# Ethernet.net
KiCad netlist of a schematic drawn in Altium Designer
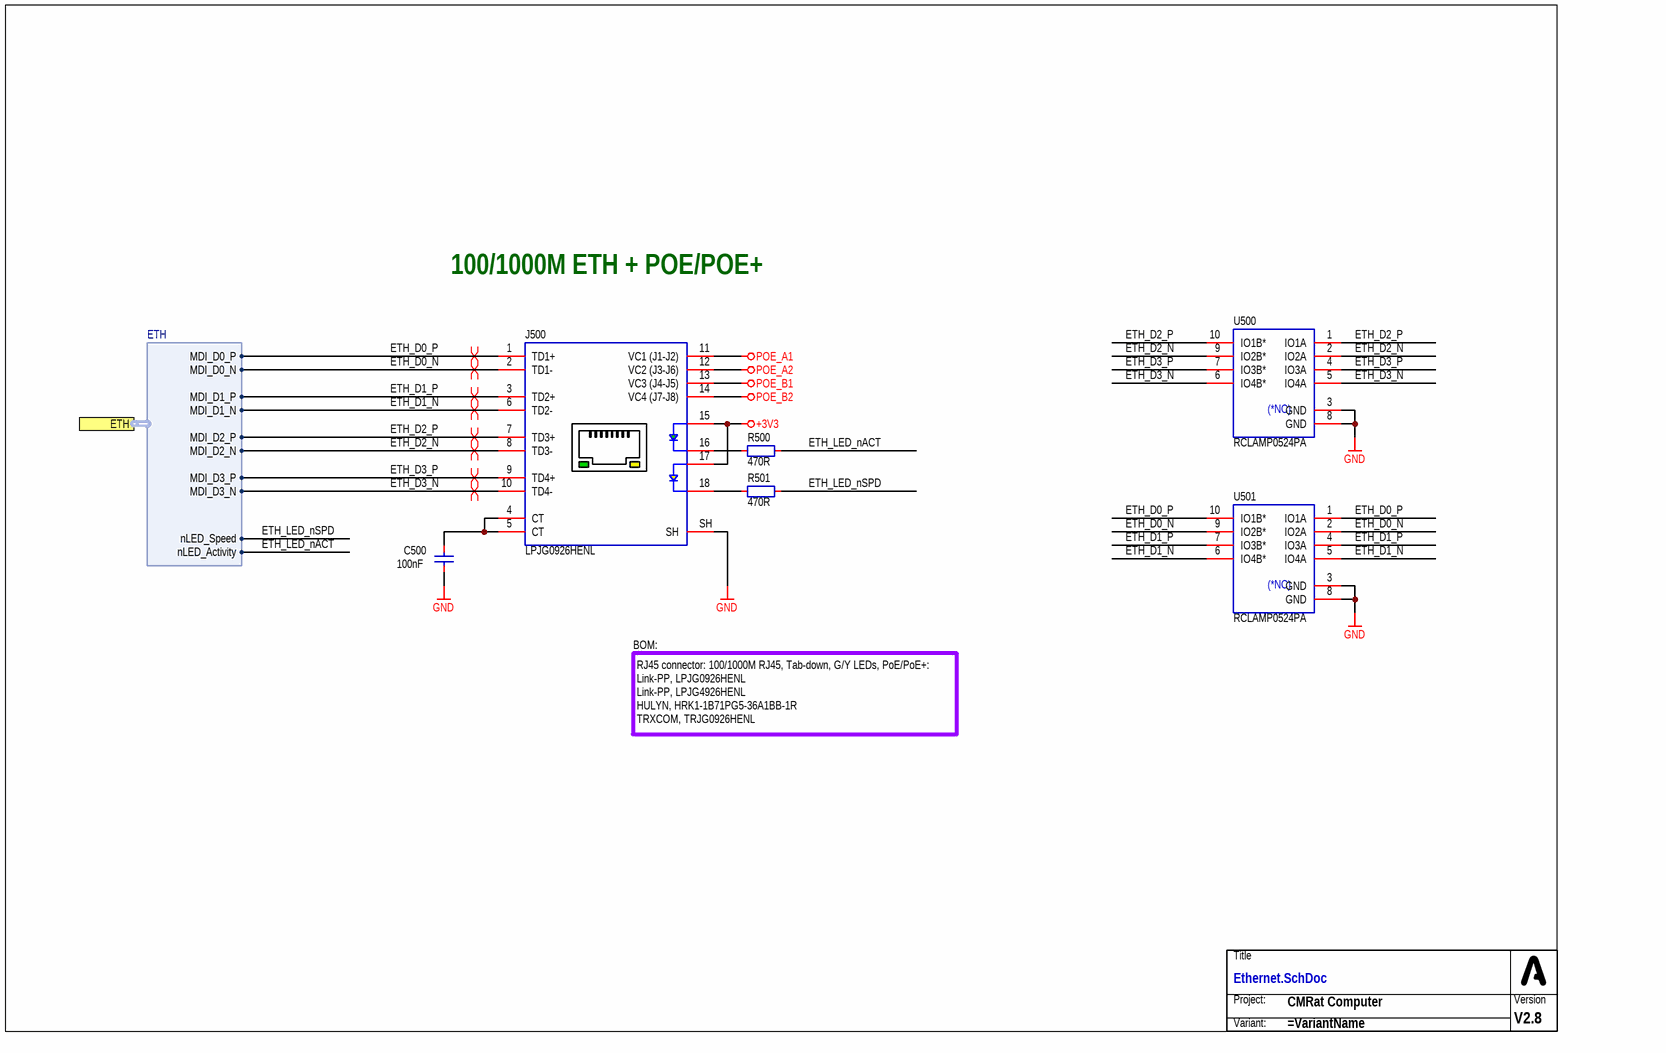
[diagram p0: Ethernet.SchDoc]

(export (version "E")
  (design (tool "Eeschema 10.0.6"))
  (components
    (comp (ref "C500")
      (value "100nF")
      (footprint "CAP_0603_R")
      (description "Capacitor; MLCC; 100nF; 10V X5R")
      (fields (field (name "MANUFACTURER") "YAGEO") (field (name "MPN") "CC0603KRX7R9BB104"))
      (libsource (lib "MirFol_db_local") (part "CAP"))
    )
    (comp (ref "J500")
      (value "LPJG0926HENL")
      (footprint "CON_LPP_LPJG0926HENL")
      (description "Connector; RJ45;")
      (fields (field (name "MANUFACTURER") "Link-PP"))
      (libsource (lib "Pineberry_Lib") (part "CON_LPP_LPJG0926HENL"))
    )
    (comp (ref "R500")
      (value "470R")
      (footprint "RES_0603_R")
      (description "Resistor; Thick Film; 470R; 1%; 100mW; 100PPM; 75V; Standard; SMD; 0603 (1608);")
      (fields (field (name "MANUFACTURER") "UNI-ROYAL(Uniroyal Elec)") (field (name "MPN") "0603WAF4700T5E"))
      (libsource (lib "MirFol_db_local") (part "RES"))
    )
    (comp (ref "R501")
      (value "470R")
      (footprint "RES_0603_R")
      (description "Resistor; Thick Film; 470R; 1%; 100mW; 100PPM; 75V; Standard; SMD; 0603 (1608);")
      (fields (field (name "MANUFACTURER") "UNI-ROYAL(Uniroyal Elec)") (field (name "MPN") "0603WAF4700T5E"))
      (libsource (lib "MirFol_db_local") (part "RES"))
    )
    (comp (ref "TB500") (value "~") (libsource (lib "Symbols_NO_BOM") (part "SCH_TITLE_BLOCK_SIMPLE_NODATE")))
    (comp (ref "U500")
      (value "RCLAMP0524PA")
      (footprint "ICC_SLP2510P8_250X100X60_P50_R")
      (description "IC; TVS Arrays; ESD Protection; 4-Channel; 17kV Air; 12kV Contact; 0.3pF Capitance; TBD; SMD; TBD;")
      (fields (field (name "MANUFACTURER") "Semtech Corporation") (field (name "MPN") "RCLAMP0524PATCT"))
      (libsource (lib "MirFol_db_local") (part "ICC_SMT_RCLAMP0524PA"))
    )
    (comp (ref "U501")
      (value "RCLAMP0524PA")
      (footprint "ICC_SLP2510P8_250X100X60_P50_R")
      (description "IC; TVS Arrays; ESD Protection; 4-Channel; 17kV Air; 12kV Contact; 0.3pF Capitance; TBD; SMD; TBD;")
      (fields (field (name "MANUFACTURER") "Semtech Corporation") (field (name "MPN") "RCLAMP0524PATCT"))
      (libsource (lib "MirFol_db_local") (part "ICC_SMT_RCLAMP0524PA"))
    )
  )
  (nets
    (net (code "2") (name "+3V3") (class "Default")
      (node (ref "J500") (pin "15") (pinfunction "GRN_A_15") (pintype "passive"))
      (node (ref "J500") (pin "17") (pinfunction "YLW_A_17") (pintype "passive"))
    )
    (net (code "3") (name "/ETH_D0_N") (class "Default")
      (node (ref "J500") (pin "2") (pinfunction "TD1-_2") (pintype "passive"))
      (node (ref "U501") (pin "2") (pinfunction "IO2A_2") (pintype "passive"))
      (node (ref "U501") (pin "9") (pinfunction "IO2B*_9") (pintype "passive"))
    )
    (net (code "4") (name "/ETH_D0_P") (class "Default")
      (node (ref "J500") (pin "1") (pinfunction "TD1+_1") (pintype "passive"))
      (node (ref "U501") (pin "1") (pinfunction "IO1A_1") (pintype "passive"))
      (node (ref "U501") (pin "10") (pinfunction "IO1B*_10") (pintype "passive"))
    )
    (net (code "5") (name "/ETH_D1_N") (class "Default")
      (node (ref "J500") (pin "6") (pinfunction "TD2-_6") (pintype "passive"))
      (node (ref "U501") (pin "5") (pinfunction "IO4A_5") (pintype "passive"))
      (node (ref "U501") (pin "6") (pinfunction "IO4B*_6") (pintype "passive"))
    )
    (net (code "6") (name "/ETH_D1_P") (class "Default")
      (node (ref "J500") (pin "3") (pinfunction "TD2+_3") (pintype "passive"))
      (node (ref "U501") (pin "4") (pinfunction "IO3A_4") (pintype "passive"))
      (node (ref "U501") (pin "7") (pinfunction "IO3B*_7") (pintype "passive"))
    )
    (net (code "7") (name "/ETH_D2_N") (class "Default")
      (node (ref "J500") (pin "8") (pinfunction "TD3-_8") (pintype "passive"))
      (node (ref "U500") (pin "2") (pinfunction "IO2A_2") (pintype "passive"))
      (node (ref "U500") (pin "9") (pinfunction "IO2B*_9") (pintype "passive"))
    )
    (net (code "8") (name "/ETH_D2_P") (class "Default")
      (node (ref "J500") (pin "7") (pinfunction "TD3+_7") (pintype "passive"))
      (node (ref "U500") (pin "1") (pinfunction "IO1A_1") (pintype "passive"))
      (node (ref "U500") (pin "10") (pinfunction "IO1B*_10") (pintype "passive"))
    )
    (net (code "9") (name "/ETH_D3_N") (class "Default")
      (node (ref "J500") (pin "10") (pinfunction "TD4-_10") (pintype "passive"))
      (node (ref "U500") (pin "5") (pinfunction "IO4A_5") (pintype "passive"))
      (node (ref "U500") (pin "6") (pinfunction "IO4B*_6") (pintype "passive"))
    )
    (net (code "10") (name "/ETH_D3_P") (class "Default")
      (node (ref "J500") (pin "9") (pinfunction "TD4+_9") (pintype "passive"))
      (node (ref "U500") (pin "4") (pinfunction "IO3A_4") (pintype "passive"))
      (node (ref "U500") (pin "7") (pinfunction "IO3B*_7") (pintype "passive"))
    )
    (net (code "11") (name "/ETH_LED_nACT") (class "Default")
      (node (ref "R500") (pin "1") (pinfunction "1_1") (pintype "passive"))
    )
    (net (code "12") (name "/ETH_LED_nSPD") (class "Default")
      (node (ref "R501") (pin "1") (pinfunction "1_1") (pintype "passive"))
    )
    (net (code "14") (name "GND") (class "Default")
      (node (ref "C500") (pin "1") (pintype "passive"))
      (node (ref "J500") (pin "SH") (pinfunction "SH_SH") (pintype "passive"))
      (node (ref "U500") (pin "3") (pinfunction "GND_3") (pintype "power_in"))
      (node (ref "U500") (pin "8") (pinfunction "GND_8") (pintype "power_in"))
      (node (ref "U501") (pin "3") (pinfunction "GND_3") (pintype "power_in"))
      (node (ref "U501") (pin "8") (pinfunction "GND_8") (pintype "power_in"))
    )
    (net (code "15") (name "Net-(C500-Pad2)") (class "Default")
      (node (ref "C500") (pin "2") (pintype "passive"))
      (node (ref "J500") (pin "4") (pinfunction "CT_4") (pintype "passive"))
      (node (ref "J500") (pin "5") (pinfunction "CT_5") (pintype "passive"))
    )
    (net (code "16") (name "Net-(J500-GRN_K)") (class "Default")
      (node (ref "J500") (pin "16") (pinfunction "GRN_K_16") (pintype "passive"))
      (node (ref "R500") (pin "2") (pinfunction "2_2") (pintype "passive"))
    )
    (net (code "17") (name "Net-(J500-YLW_K)") (class "Default")
      (node (ref "J500") (pin "18") (pinfunction "YLW_K_18") (pintype "passive"))
      (node (ref "R501") (pin "2") (pinfunction "2_2") (pintype "passive"))
    )
    (net (code "18") (name "POE_A1") (class "Default")
      (node (ref "J500") (pin "11") (pinfunction "VC1_(J1-J2)_11") (pintype "passive"))
    )
    (net (code "19") (name "POE_A2") (class "Default")
      (node (ref "J500") (pin "12") (pinfunction "VC2_(J3-J6)_12") (pintype "passive"))
    )
    (net (code "20") (name "POE_B1") (class "Default")
      (node (ref "J500") (pin "13") (pinfunction "VC3_(J4-J5)_13") (pintype "passive"))
    )
    (net (code "21") (name "POE_B2") (class "Default")
      (node (ref "J500") (pin "14") (pinfunction "VC4_(J7-J8)_14") (pintype "passive"))
    )
  )
)
